# arduino.net
KiCad netlist of a schematic drawn in EAGLE
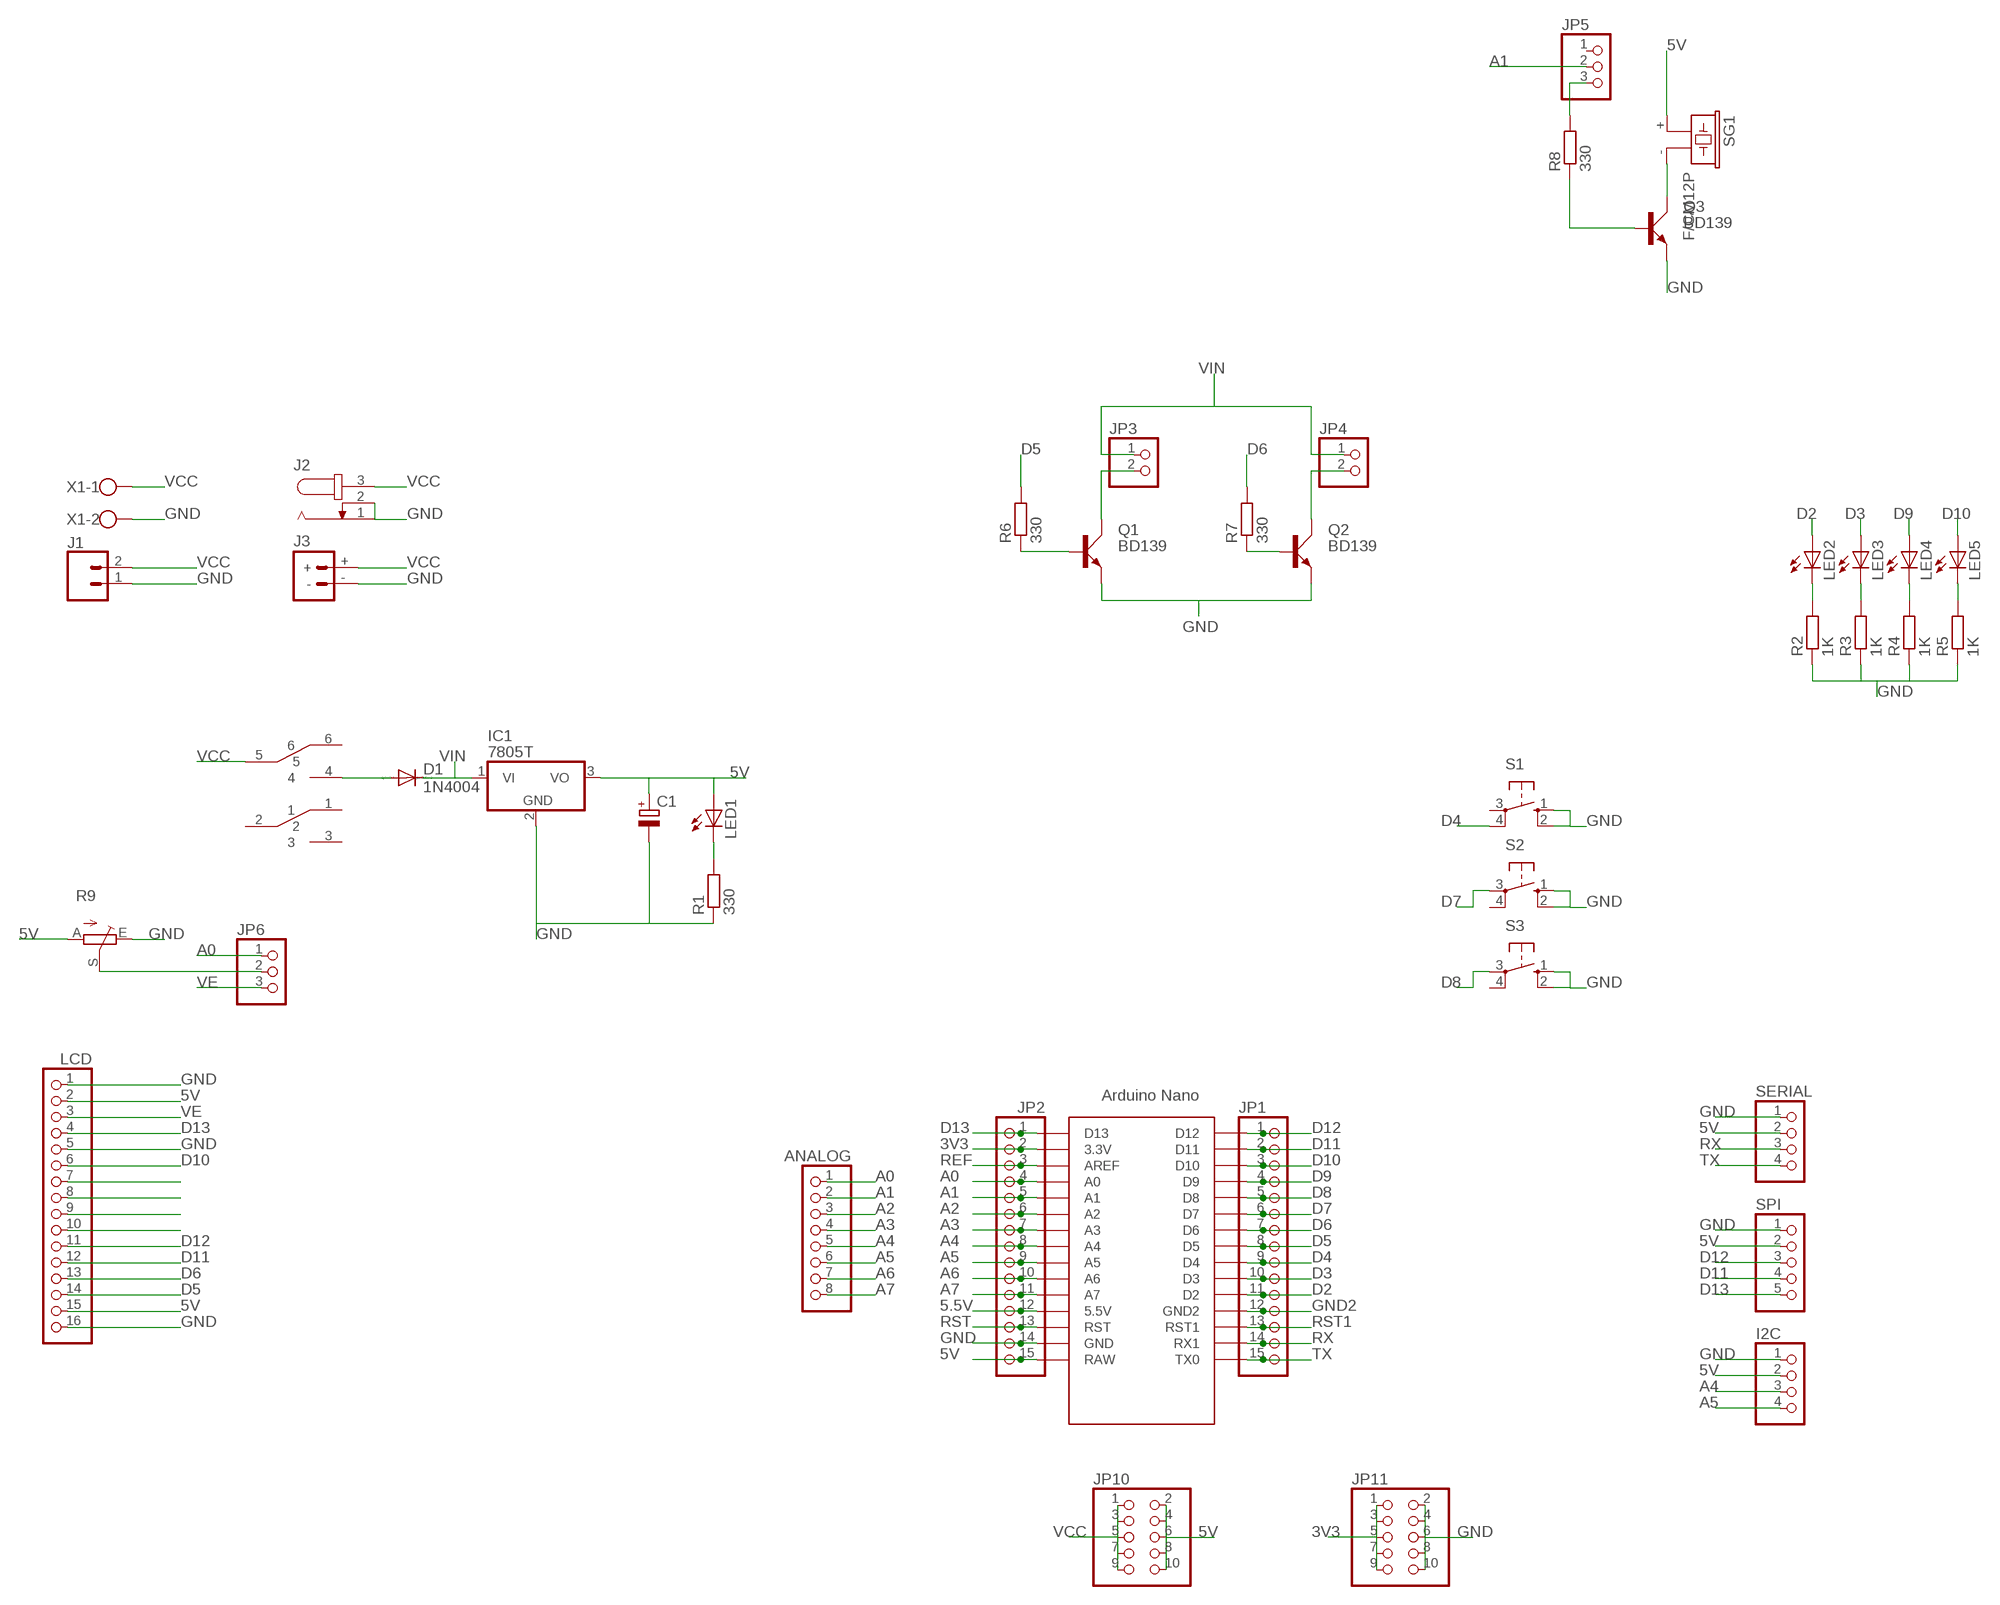
[diagram p0: schematic, sheet 1]

(export (version "E")
  (design (tool "Eeschema 10.0.6"))
  (components
    (comp (ref "ANALOG")
      (value "PINHD-1X8")
      (footprint "eagle-import:1X08")
      (libsource (lib "eagle-import") (part "PINHD-1X8"))
    )
    (comp (ref "C1")
      (value "CPOL-EUE5-8.5")
      (footprint "eagle-import:E5-8,5")
      (libsource (lib "eagle-import") (part "CPOL-EUE5-8.5"))
    )
    (comp (ref "D1")
      (value "1N4004")
      (footprint "eagle-import:DO41-10")
      (libsource (lib "eagle-import") (part "1N4004"))
    )
    (comp (ref "I2C")
      (value "PINHD-1X4")
      (footprint "eagle-import:1X04")
      (libsource (lib "eagle-import") (part "PINHD-1X4"))
    )
    (comp (ref "IC1")
      (value "7805T")
      (footprint "eagle-import:TO220H")
      (libsource (lib "eagle-import") (part "78T05"))
    )
    (comp (ref "J1")
      (value "CONN_02POLAR_LOCK")
      (footprint "eagle-import:MOLEX-1X2_LOCK")
      (libsource (lib "eagle-import") (part "CONN_02POLAR_LOCK"))
    )
    (comp (ref "J2")
      (value "JACK-PLUG0")
      (footprint "eagle-import:SPC4077")
      (libsource (lib "eagle-import") (part "JACK-PLUG0"))
    )
    (comp (ref "J3")
      (value "BATTERY_CONN_DEANS")
      (footprint "eagle-import:DEANS")
      (libsource (lib "eagle-import") (part "BATTERY_CONN_DEANS"))
    )
    (comp (ref "JP1")
      (value "PINHD-1X15")
      (footprint "eagle-import:1X15")
      (libsource (lib "eagle-import") (part "PINHD-1X15"))
    )
    (comp (ref "JP2")
      (value "PINHD-1X15")
      (footprint "eagle-import:1X15")
      (libsource (lib "eagle-import") (part "PINHD-1X15"))
    )
    (comp (ref "JP3")
      (value "PINHD-1X2")
      (footprint "eagle-import:1X02")
      (libsource (lib "eagle-import") (part "PINHD-1X2"))
    )
    (comp (ref "JP4")
      (value "PINHD-1X2")
      (footprint "eagle-import:1X02")
      (libsource (lib "eagle-import") (part "PINHD-1X2"))
    )
    (comp (ref "JP5")
      (value "PINHD-1X3")
      (footprint "eagle-import:1X03")
      (libsource (lib "eagle-import") (part "PINHD-1X3"))
    )
    (comp (ref "JP6")
      (value "PINHD-1X3")
      (footprint "eagle-import:1X03")
      (libsource (lib "eagle-import") (part "PINHD-1X3"))
    )
    (comp (ref "JP10")
      (value "PINHD-2X5")
      (footprint "eagle-import:2X05")
      (libsource (lib "eagle-import") (part "PINHD-2X5"))
    )
    (comp (ref "JP11")
      (value "PINHD-2X5")
      (footprint "eagle-import:2X05")
      (libsource (lib "eagle-import") (part "PINHD-2X5"))
    )
    (comp (ref "LCD")
      (value "PINHD-1X16")
      (footprint "eagle-import:1X16")
      (libsource (lib "eagle-import") (part "PINHD-1X16"))
    )
    (comp (ref "LED1")
      (value "LED3MM")
      (footprint "eagle-import:LED3MM")
      (libsource (lib "eagle-import") (part "LED3MM"))
    )
    (comp (ref "LED2")
      (value "LED3MM")
      (footprint "eagle-import:LED3MM")
      (libsource (lib "eagle-import") (part "LED3MM"))
    )
    (comp (ref "LED3")
      (value "LED3MM")
      (footprint "eagle-import:LED3MM")
      (libsource (lib "eagle-import") (part "LED3MM"))
    )
    (comp (ref "LED4")
      (value "LED3MM")
      (footprint "eagle-import:LED3MM")
      (libsource (lib "eagle-import") (part "LED3MM"))
    )
    (comp (ref "LED5")
      (value "LED3MM")
      (footprint "eagle-import:LED3MM")
      (libsource (lib "eagle-import") (part "LED3MM"))
    )
    (comp (ref "Q1")
      (value "BD139")
      (footprint "eagle-import:TO126AV")
      (libsource (lib "eagle-import") (part "BD139"))
    )
    (comp (ref "Q2")
      (value "BD139")
      (footprint "eagle-import:TO126AV")
      (libsource (lib "eagle-import") (part "BD139"))
    )
    (comp (ref "Q3")
      (value "BD139")
      (footprint "eagle-import:TO126AV")
      (libsource (lib "eagle-import") (part "BD139"))
    )
    (comp (ref "R1")
      (value "330")
      (footprint "eagle-import:0207_7")
      (libsource (lib "eagle-import") (part "R-EU_0207/7"))
    )
    (comp (ref "R2")
      (value "1K")
      (footprint "eagle-import:0207_7")
      (libsource (lib "eagle-import") (part "R-EU_0207/7"))
    )
    (comp (ref "R3")
      (value "1K")
      (footprint "eagle-import:0207_7")
      (libsource (lib "eagle-import") (part "R-EU_0207/7"))
    )
    (comp (ref "R4")
      (value "1K")
      (footprint "eagle-import:0207_7")
      (libsource (lib "eagle-import") (part "R-EU_0207/7"))
    )
    (comp (ref "R5")
      (value "1K")
      (footprint "eagle-import:0207_7")
      (libsource (lib "eagle-import") (part "R-EU_0207/7"))
    )
    (comp (ref "R6")
      (value "330")
      (footprint "eagle-import:0207_7")
      (libsource (lib "eagle-import") (part "R-EU_0207/7"))
    )
    (comp (ref "R7")
      (value "330")
      (footprint "eagle-import:0207_7")
      (libsource (lib "eagle-import") (part "R-EU_0207/7"))
    )
    (comp (ref "R8")
      (value "330")
      (footprint "eagle-import:0207_7")
      (libsource (lib "eagle-import") (part "R-EU_0207/7"))
    )
    (comp (ref "R9")
      (value "TRIM_EU-CA6V")
      (footprint "eagle-import:CA6V")
      (libsource (lib "eagle-import") (part "TRIM_EU-CA6V"))
    )
    (comp (ref "S1")
      (value "10-XX")
      (footprint "eagle-import:B3F-10XX")
      (fields (field (name "MPN") "B3F-1000"))
      (libsource (lib "eagle-import") (part "10-XX"))
    )
    (comp (ref "S2")
      (value "10-XX")
      (footprint "eagle-import:B3F-10XX")
      (fields (field (name "MPN") "B3F-1000"))
      (libsource (lib "eagle-import") (part "10-XX"))
    )
    (comp (ref "S3")
      (value "10-XX")
      (footprint "eagle-import:B3F-10XX")
      (fields (field (name "MPN") "B3F-1000"))
      (libsource (lib "eagle-import") (part "10-XX"))
    )
    (comp (ref "SERIAL")
      (value "PINHD-1X4")
      (footprint "eagle-import:1X04")
      (libsource (lib "eagle-import") (part "PINHD-1X4"))
    )
    (comp (ref "SG1")
      (value "F/CM12P")
      (footprint "eagle-import:F_CM12P")
      (libsource (lib "eagle-import") (part "F/CM12P"))
    )
    (comp (ref "SPI")
      (value "PINHD-1X5")
      (footprint "eagle-import:1X05")
      (libsource (lib "eagle-import") (part "PINHD-1X5"))
    )
    (comp (ref "U$1")
      (value "NANO")
      (footprint "eagle-import:NANO")
      (libsource (lib "eagle-import") (part "NANO"))
    )
    (comp (ref "U$2")
      (value "BUTTON-DPDT-7MM")
      (footprint "eagle-import:BUTTON-DPDT-7MM")
      (libsource (lib "eagle-import") (part "BUTTON-DPDT-7MM"))
    )
    (comp (ref "X1")
      (value "W237-102")
      (footprint "eagle-import:W237-102")
      (fields (field (name "MPN") "237-102"))
      (libsource (lib "eagle-import") (part "W237-102"))
    )
  )
  (nets
    (net (code "1") (name "/3V3") (class "Default")
      (node (ref "JP11") (pin "1") (pinfunction "1_1") (pintype "passive"))
      (node (ref "JP11") (pin "3") (pinfunction "3_3") (pintype "passive"))
      (node (ref "JP11") (pin "5") (pinfunction "5_5") (pintype "passive"))
      (node (ref "JP11") (pin "7") (pinfunction "7_7") (pintype "passive"))
      (node (ref "JP11") (pin "9") (pinfunction "9_9") (pintype "passive"))
      (node (ref "JP2") (pin "2") (pinfunction "2_2") (pintype "passive"))
      (node (ref "U$1") (pin "3.3V") (pinfunction "3.3V_3.3V") (pintype "bidirectional"))
    )
    (net (code "2") (name "/5.5V") (class "Default")
      (node (ref "JP2") (pin "12") (pinfunction "12_12") (pintype "passive"))
      (node (ref "U$1") (pin "5V") (pinfunction "5.5V_5V") (pintype "bidirectional"))
    )
    (net (code "3") (name "/5V") (class "Default")
      (node (ref "C1") (pin "+") (pinfunction "+_+") (pintype "passive"))
      (node (ref "I2C") (pin "2") (pinfunction "2_2") (pintype "passive"))
      (node (ref "IC1") (pin "3") (pinfunction "VO_3") (pintype "passive"))
      (node (ref "JP10") (pin "10") (pinfunction "10_10") (pintype "passive"))
      (node (ref "JP10") (pin "2") (pinfunction "2_2") (pintype "passive"))
      (node (ref "JP10") (pin "4") (pinfunction "4_4") (pintype "passive"))
      (node (ref "JP10") (pin "6") (pinfunction "6_6") (pintype "passive"))
      (node (ref "JP10") (pin "8") (pinfunction "8_8") (pintype "passive"))
      (node (ref "JP2") (pin "15") (pinfunction "15_15") (pintype "passive"))
      (node (ref "LCD") (pin "15") (pinfunction "15_15") (pintype "passive"))
      (node (ref "LCD") (pin "2") (pinfunction "2_2") (pintype "passive"))
      (node (ref "LED1") (pin "A") (pinfunction "A_A") (pintype "passive"))
      (node (ref "R9") (pin "A") (pinfunction "A_A") (pintype "passive"))
      (node (ref "SERIAL") (pin "2") (pinfunction "2_2") (pintype "passive"))
      (node (ref "SG1") (pin "+") (pinfunction "1_+") (pintype "passive"))
      (node (ref "SPI") (pin "2") (pinfunction "2_2") (pintype "passive"))
      (node (ref "U$1") (pin "RAW") (pinfunction "RAW_RAW") (pintype "bidirectional"))
    )
    (net (code "4") (name "/A0") (class "Default")
      (node (ref "ANALOG") (pin "1") (pinfunction "1_1") (pintype "passive"))
      (node (ref "JP2") (pin "4") (pinfunction "4_4") (pintype "passive"))
      (node (ref "JP6") (pin "1") (pinfunction "1_1") (pintype "passive"))
      (node (ref "U$1") (pin "A0") (pinfunction "A0_A0") (pintype "bidirectional"))
    )
    (net (code "5") (name "/A1") (class "Default")
      (node (ref "ANALOG") (pin "2") (pinfunction "2_2") (pintype "passive"))
      (node (ref "JP2") (pin "5") (pinfunction "5_5") (pintype "passive"))
      (node (ref "JP5") (pin "2") (pinfunction "2_2") (pintype "passive"))
      (node (ref "U$1") (pin "A1") (pinfunction "A1_A1") (pintype "bidirectional"))
    )
    (net (code "6") (name "/A2") (class "Default")
      (node (ref "ANALOG") (pin "3") (pinfunction "3_3") (pintype "passive"))
      (node (ref "JP2") (pin "6") (pinfunction "6_6") (pintype "passive"))
      (node (ref "U$1") (pin "A2") (pinfunction "A2_A2") (pintype "bidirectional"))
    )
    (net (code "7") (name "/A3") (class "Default")
      (node (ref "ANALOG") (pin "4") (pinfunction "4_4") (pintype "passive"))
      (node (ref "JP2") (pin "7") (pinfunction "7_7") (pintype "passive"))
      (node (ref "U$1") (pin "A3") (pinfunction "A3_A3") (pintype "bidirectional"))
    )
    (net (code "8") (name "/A4") (class "Default")
      (node (ref "ANALOG") (pin "5") (pinfunction "5_5") (pintype "passive"))
      (node (ref "I2C") (pin "3") (pinfunction "3_3") (pintype "passive"))
      (node (ref "JP2") (pin "8") (pinfunction "8_8") (pintype "passive"))
      (node (ref "U$1") (pin "A4") (pinfunction "A4_A4") (pintype "bidirectional"))
    )
    (net (code "9") (name "/A5") (class "Default")
      (node (ref "ANALOG") (pin "6") (pinfunction "6_6") (pintype "passive"))
      (node (ref "I2C") (pin "4") (pinfunction "4_4") (pintype "passive"))
      (node (ref "JP2") (pin "9") (pinfunction "9_9") (pintype "passive"))
      (node (ref "U$1") (pin "A5") (pinfunction "A5_A5") (pintype "bidirectional"))
    )
    (net (code "10") (name "/A6") (class "Default")
      (node (ref "ANALOG") (pin "7") (pinfunction "7_7") (pintype "passive"))
      (node (ref "JP2") (pin "10") (pinfunction "10_10") (pintype "passive"))
      (node (ref "U$1") (pin "A6") (pinfunction "A6_A6") (pintype "bidirectional"))
    )
    (net (code "11") (name "/A7") (class "Default")
      (node (ref "ANALOG") (pin "8") (pinfunction "8_8") (pintype "passive"))
      (node (ref "JP2") (pin "11") (pinfunction "11_11") (pintype "passive"))
      (node (ref "U$1") (pin "A7") (pinfunction "A7_A7") (pintype "bidirectional"))
    )
    (net (code "12") (name "/D2") (class "Default")
      (node (ref "JP1") (pin "11") (pinfunction "11_11") (pintype "passive"))
      (node (ref "LED2") (pin "A") (pinfunction "A_A") (pintype "passive"))
      (node (ref "U$1") (pin "D2") (pinfunction "D2_D2") (pintype "bidirectional"))
    )
    (net (code "13") (name "/D3") (class "Default")
      (node (ref "JP1") (pin "10") (pinfunction "10_10") (pintype "passive"))
      (node (ref "LED3") (pin "A") (pinfunction "A_A") (pintype "passive"))
      (node (ref "U$1") (pin "D3") (pinfunction "D3_D3") (pintype "bidirectional"))
    )
    (net (code "14") (name "/D4") (class "Default")
      (node (ref "JP1") (pin "9") (pinfunction "9_9") (pintype "passive"))
      (node (ref "S1") (pin "4") (pinfunction "P1_4") (pintype "passive"))
      (node (ref "U$1") (pin "D4") (pinfunction "D4_D4") (pintype "bidirectional"))
    )
    (net (code "15") (name "/D5") (class "Default")
      (node (ref "JP1") (pin "8") (pinfunction "8_8") (pintype "passive"))
      (node (ref "LCD") (pin "14") (pinfunction "14_14") (pintype "passive"))
      (node (ref "R6") (pin "2") (pinfunction "2_2") (pintype "passive"))
      (node (ref "U$1") (pin "D5") (pinfunction "D5_D5") (pintype "bidirectional"))
    )
    (net (code "16") (name "/D6") (class "Default")
      (node (ref "JP1") (pin "7") (pinfunction "7_7") (pintype "passive"))
      (node (ref "LCD") (pin "13") (pinfunction "13_13") (pintype "passive"))
      (node (ref "R7") (pin "2") (pinfunction "2_2") (pintype "passive"))
      (node (ref "U$1") (pin "D6") (pinfunction "D6_D6") (pintype "bidirectional"))
    )
    (net (code "17") (name "/D7") (class "Default")
      (node (ref "JP1") (pin "6") (pinfunction "6_6") (pintype "passive"))
      (node (ref "S2") (pin "3") (pinfunction "P_3") (pintype "passive"))
      (node (ref "U$1") (pin "D7") (pinfunction "D7_D7") (pintype "bidirectional"))
    )
    (net (code "18") (name "/D8") (class "Default")
      (node (ref "JP1") (pin "5") (pinfunction "5_5") (pintype "passive"))
      (node (ref "S3") (pin "3") (pinfunction "P_3") (pintype "passive"))
      (node (ref "U$1") (pin "D8") (pinfunction "D8_D8") (pintype "bidirectional"))
    )
    (net (code "19") (name "/D9") (class "Default")
      (node (ref "JP1") (pin "4") (pinfunction "4_4") (pintype "passive"))
      (node (ref "LED4") (pin "A") (pinfunction "A_A") (pintype "passive"))
      (node (ref "U$1") (pin "D9") (pinfunction "D9_D9") (pintype "bidirectional"))
    )
    (net (code "20") (name "/D10") (class "Default")
      (node (ref "JP1") (pin "3") (pinfunction "3_3") (pintype "passive"))
      (node (ref "LCD") (pin "6") (pinfunction "6_6") (pintype "passive"))
      (node (ref "LED5") (pin "A") (pinfunction "A_A") (pintype "passive"))
      (node (ref "U$1") (pin "D10") (pinfunction "D10_D10") (pintype "bidirectional"))
    )
    (net (code "21") (name "/D11") (class "Default")
      (node (ref "JP1") (pin "2") (pinfunction "2_2") (pintype "passive"))
      (node (ref "LCD") (pin "12") (pinfunction "12_12") (pintype "passive"))
      (node (ref "SPI") (pin "4") (pinfunction "4_4") (pintype "passive"))
      (node (ref "U$1") (pin "D11") (pinfunction "D11_D11") (pintype "bidirectional"))
    )
    (net (code "22") (name "/D12") (class "Default")
      (node (ref "JP1") (pin "1") (pinfunction "1_1") (pintype "passive"))
      (node (ref "LCD") (pin "11") (pinfunction "11_11") (pintype "passive"))
      (node (ref "SPI") (pin "3") (pinfunction "3_3") (pintype "passive"))
      (node (ref "U$1") (pin "D12") (pinfunction "D12_D12") (pintype "bidirectional"))
    )
    (net (code "23") (name "/D13") (class "Default")
      (node (ref "JP2") (pin "1") (pinfunction "1_1") (pintype "passive"))
      (node (ref "LCD") (pin "4") (pinfunction "4_4") (pintype "passive"))
      (node (ref "SPI") (pin "5") (pinfunction "5_5") (pintype "passive"))
      (node (ref "U$1") (pin "D13") (pinfunction "D13_D13") (pintype "bidirectional"))
    )
    (net (code "24") (name "/GND") (class "Default")
      (node (ref "C1") (pin "-") (pinfunction "-_-") (pintype "passive"))
      (node (ref "I2C") (pin "1") (pinfunction "1_1") (pintype "passive"))
      (node (ref "IC1") (pin "2") (pinfunction "GND_2") (pintype "passive"))
      (node (ref "J1") (pin "1") (pinfunction "1_1") (pintype "passive"))
      (node (ref "J2") (pin "1") (pinfunction "1_1") (pintype "passive"))
      (node (ref "J2") (pin "2") (pinfunction "2_2") (pintype "passive"))
      (node (ref "J3") (pin "-") (pinfunction "-_-") (pintype "passive"))
      (node (ref "JP11") (pin "10") (pinfunction "10_10") (pintype "passive"))
      (node (ref "JP11") (pin "2") (pinfunction "2_2") (pintype "passive"))
      (node (ref "JP11") (pin "4") (pinfunction "4_4") (pintype "passive"))
      (node (ref "JP11") (pin "6") (pinfunction "6_6") (pintype "passive"))
      (node (ref "JP11") (pin "8") (pinfunction "8_8") (pintype "passive"))
      (node (ref "JP2") (pin "14") (pinfunction "14_14") (pintype "passive"))
      (node (ref "LCD") (pin "1") (pinfunction "1_1") (pintype "passive"))
      (node (ref "LCD") (pin "16") (pinfunction "16_16") (pintype "passive"))
      (node (ref "LCD") (pin "5") (pinfunction "5_5") (pintype "passive"))
      (node (ref "Q1") (pin "E") (pinfunction "E_E") (pintype "passive"))
      (node (ref "Q2") (pin "E") (pinfunction "E_E") (pintype "passive"))
      (node (ref "Q3") (pin "E") (pinfunction "E_E") (pintype "passive"))
      (node (ref "R1") (pin "1") (pinfunction "1_1") (pintype "passive"))
      (node (ref "R2") (pin "1") (pinfunction "1_1") (pintype "passive"))
      (node (ref "R3") (pin "1") (pinfunction "1_1") (pintype "passive"))
      (node (ref "R4") (pin "1") (pinfunction "1_1") (pintype "passive"))
      (node (ref "R5") (pin "1") (pinfunction "1_1") (pintype "passive"))
      (node (ref "R9") (pin "E") (pinfunction "E_E") (pintype "passive"))
      (node (ref "S1") (pin "1") (pinfunction "S_1") (pintype "passive"))
      (node (ref "S1") (pin "2") (pinfunction "S1_2") (pintype "passive"))
      (node (ref "S2") (pin "1") (pinfunction "S_1") (pintype "passive"))
      (node (ref "S2") (pin "2") (pinfunction "S1_2") (pintype "passive"))
      (node (ref "S3") (pin "1") (pinfunction "S_1") (pintype "passive"))
      (node (ref "S3") (pin "2") (pinfunction "S1_2") (pintype "passive"))
      (node (ref "SERIAL") (pin "1") (pinfunction "1_1") (pintype "passive"))
      (node (ref "SPI") (pin "1") (pinfunction "1_1") (pintype "passive"))
      (node (ref "U$1") (pin "GND") (pinfunction "GND_GND") (pintype "bidirectional"))
      (node (ref "X1") (pin "2") (pinfunction "KL_2") (pintype "passive"))
    )
    (net (code "25") (name "/GND2") (class "Default")
      (node (ref "JP1") (pin "12") (pinfunction "12_12") (pintype "passive"))
      (node (ref "U$1") (pin "GND1") (pinfunction "GND2_GND1") (pintype "bidirectional"))
    )
    (net (code "26") (name "/REF") (class "Default")
      (node (ref "JP2") (pin "3") (pinfunction "3_3") (pintype "passive"))
      (node (ref "U$1") (pin "AREF") (pinfunction "AREF_AREF") (pintype "bidirectional"))
    )
    (net (code "27") (name "/RST") (class "Default")
      (node (ref "JP2") (pin "13") (pinfunction "13_13") (pintype "passive"))
      (node (ref "U$1") (pin "RST") (pinfunction "RST_RST") (pintype "bidirectional"))
    )
    (net (code "28") (name "/RST1") (class "Default")
      (node (ref "JP1") (pin "13") (pinfunction "13_13") (pintype "passive"))
      (node (ref "U$1") (pin "RST1") (pinfunction "RST1_RST1") (pintype "bidirectional"))
    )
    (net (code "29") (name "/RX") (class "Default")
      (node (ref "JP1") (pin "14") (pinfunction "14_14") (pintype "passive"))
      (node (ref "SERIAL") (pin "3") (pinfunction "3_3") (pintype "passive"))
      (node (ref "U$1") (pin "RX1") (pinfunction "RX1_RX1") (pintype "bidirectional"))
    )
    (net (code "30") (name "/TX") (class "Default")
      (node (ref "JP1") (pin "15") (pinfunction "15_15") (pintype "passive"))
      (node (ref "SERIAL") (pin "4") (pinfunction "4_4") (pintype "passive"))
      (node (ref "U$1") (pin "TX0") (pinfunction "TX0_TX0") (pintype "bidirectional"))
    )
    (net (code "31") (name "/VCC") (class "Default")
      (node (ref "J1") (pin "2") (pinfunction "2_2") (pintype "passive"))
      (node (ref "J2") (pin "3") (pinfunction "3_3") (pintype "passive"))
      (node (ref "J3") (pin "+") (pinfunction "+_+") (pintype "passive"))
      (node (ref "JP10") (pin "1") (pinfunction "1_1") (pintype "passive"))
      (node (ref "JP10") (pin "3") (pinfunction "3_3") (pintype "passive"))
      (node (ref "JP10") (pin "5") (pinfunction "5_5") (pintype "passive"))
      (node (ref "JP10") (pin "7") (pinfunction "7_7") (pintype "passive"))
      (node (ref "JP10") (pin "9") (pinfunction "9_9") (pintype "passive"))
      (node (ref "U$2") (pin "5") (pinfunction "5_5") (pintype "bidirectional"))
      (node (ref "X1") (pin "1") (pinfunction "KL_1") (pintype "passive"))
    )
    (net (code "32") (name "/VE") (class "Default")
      (node (ref "JP6") (pin "3") (pinfunction "3_3") (pintype "passive"))
      (node (ref "LCD") (pin "3") (pinfunction "3_3") (pintype "passive"))
    )
    (net (code "33") (name "/VIN") (class "Default")
      (node (ref "D1") (pin "C") (pinfunction "C_C") (pintype "passive"))
      (node (ref "IC1") (pin "1") (pinfunction "VI_1") (pintype "input"))
      (node (ref "JP3") (pin "1") (pinfunction "1_1") (pintype "passive"))
      (node (ref "JP4") (pin "1") (pinfunction "1_1") (pintype "passive"))
    )
    (net (code "34") (name "Net-(D1-PadA)") (class "Default")
      (node (ref "D1") (pin "A") (pinfunction "A_A") (pintype "passive"))
      (node (ref "U$2") (pin "4") (pinfunction "4_4") (pintype "bidirectional"))
    )
    (net (code "35") (name "Net-(JP3-Pad2)") (class "Default")
      (node (ref "JP3") (pin "2") (pinfunction "2_2") (pintype "passive"))
      (node (ref "Q1") (pin "C") (pinfunction "C_C") (pintype "passive"))
    )
    (net (code "36") (name "Net-(JP4-Pad2)") (class "Default")
      (node (ref "JP4") (pin "2") (pinfunction "2_2") (pintype "passive"))
      (node (ref "Q2") (pin "C") (pinfunction "C_C") (pintype "passive"))
    )
    (net (code "37") (name "Net-(JP5-Pad3)") (class "Default")
      (node (ref "JP5") (pin "3") (pinfunction "3_3") (pintype "passive"))
      (node (ref "R8") (pin "2") (pinfunction "2_2") (pintype "passive"))
    )
    (net (code "38") (name "Net-(JP6-Pad2)") (class "Default")
      (node (ref "JP6") (pin "2") (pinfunction "2_2") (pintype "passive"))
      (node (ref "R9") (pin "S") (pinfunction "S_S") (pintype "passive"))
    )
    (net (code "39") (name "Net-(LED1-C)") (class "Default")
      (node (ref "LED1") (pin "K") (pinfunction "C_K") (pintype "passive"))
      (node (ref "R1") (pin "2") (pinfunction "2_2") (pintype "passive"))
    )
    (net (code "40") (name "Net-(LED2-C)") (class "Default")
      (node (ref "LED2") (pin "K") (pinfunction "C_K") (pintype "passive"))
      (node (ref "R2") (pin "2") (pinfunction "2_2") (pintype "passive"))
    )
    (net (code "41") (name "Net-(LED3-C)") (class "Default")
      (node (ref "LED3") (pin "K") (pinfunction "C_K") (pintype "passive"))
      (node (ref "R3") (pin "2") (pinfunction "2_2") (pintype "passive"))
    )
    (net (code "42") (name "Net-(LED4-C)") (class "Default")
      (node (ref "LED4") (pin "K") (pinfunction "C_K") (pintype "passive"))
      (node (ref "R4") (pin "2") (pinfunction "2_2") (pintype "passive"))
    )
    (net (code "43") (name "Net-(LED5-C)") (class "Default")
      (node (ref "LED5") (pin "K") (pinfunction "C_K") (pintype "passive"))
      (node (ref "R5") (pin "2") (pinfunction "2_2") (pintype "passive"))
    )
    (net (code "44") (name "Net-(Q1-PadB)") (class "Default")
      (node (ref "Q1") (pin "B") (pinfunction "B_B") (pintype "passive"))
      (node (ref "R6") (pin "1") (pinfunction "1_1") (pintype "passive"))
    )
    (net (code "45") (name "Net-(Q2-PadB)") (class "Default")
      (node (ref "Q2") (pin "B") (pinfunction "B_B") (pintype "passive"))
      (node (ref "R7") (pin "1") (pinfunction "1_1") (pintype "passive"))
    )
    (net (code "46") (name "Net-(Q3-PadB)") (class "Default")
      (node (ref "Q3") (pin "B") (pinfunction "B_B") (pintype "passive"))
      (node (ref "R8") (pin "1") (pinfunction "1_1") (pintype "passive"))
    )
    (net (code "47") (name "Net-(SG1-2)") (class "Default")
      (node (ref "Q3") (pin "C") (pinfunction "C_C") (pintype "passive"))
      (node (ref "SG1") (pin "-") (pinfunction "2_-") (pintype "passive"))
    )
    (net (code "48") (name "unconnected-(JP5-Pad1)") (class "Default")
      (node (ref "JP5") (pin "1") (pinfunction "1_1") (pintype "passive"))
    )
    (net (code "49") (name "unconnected-(LCD-Pad7)") (class "Default")
      (node (ref "LCD") (pin "7") (pinfunction "7_7") (pintype "passive"))
    )
    (net (code "50") (name "unconnected-(LCD-Pad8)") (class "Default")
      (node (ref "LCD") (pin "8") (pinfunction "8_8") (pintype "passive"))
    )
    (net (code "51") (name "unconnected-(LCD-Pad9)") (class "Default")
      (node (ref "LCD") (pin "9") (pinfunction "9_9") (pintype "passive"))
    )
    (net (code "52") (name "unconnected-(LCD-Pad10)") (class "Default")
      (node (ref "LCD") (pin "10") (pinfunction "10_10") (pintype "passive"))
    )
    (net (code "53") (name "unconnected-(S1-P-Pad3)") (class "Default")
      (node (ref "S1") (pin "3") (pinfunction "P_3") (pintype "passive"))
    )
    (net (code "54") (name "unconnected-(S2-P1-Pad4)") (class "Default")
      (node (ref "S2") (pin "4") (pinfunction "P1_4") (pintype "passive"))
    )
    (net (code "55") (name "unconnected-(S3-P1-Pad4)") (class "Default")
      (node (ref "S3") (pin "4") (pinfunction "P1_4") (pintype "passive"))
    )
    (net (code "56") (name "unconnected-(U$1-PadICSP1)") (class "Default")
      (node (ref "U$1") (pin "ICSP1") (pinfunction "ICSP1_ICSP1") (pintype "bidirectional"))
    )
    (net (code "57") (name "unconnected-(U$1-PadICSP2)") (class "Default")
      (node (ref "U$1") (pin "ICSP2") (pinfunction "ICSP2_ICSP2") (pintype "bidirectional"))
    )
    (net (code "58") (name "unconnected-(U$1-PadICSP3)") (class "Default")
      (node (ref "U$1") (pin "ICSP3") (pinfunction "ICSP3_ICSP3") (pintype "bidirectional"))
    )
    (net (code "59") (name "unconnected-(U$1-PadICSP4)") (class "Default")
      (node (ref "U$1") (pin "ICSP4") (pinfunction "ICSP4_ICSP4") (pintype "bidirectional"))
    )
    (net (code "60") (name "unconnected-(U$1-PadICSP5)") (class "Default")
      (node (ref "U$1") (pin "ICSP5") (pinfunction "ICSP5_ICSP5") (pintype "bidirectional"))
    )
    (net (code "61") (name "unconnected-(U$1-PadICSP6)") (class "Default")
      (node (ref "U$1") (pin "ICSP6") (pinfunction "ICSP6_ICSP6") (pintype "bidirectional"))
    )
    (net (code "62") (name "unconnected-(U$2-Pad1)") (class "Default")
      (node (ref "U$2") (pin "1") (pinfunction "1_1") (pintype "bidirectional"))
    )
    (net (code "63") (name "unconnected-(U$2-Pad2)") (class "Default")
      (node (ref "U$2") (pin "2") (pinfunction "2_2") (pintype "bidirectional"))
    )
    (net (code "64") (name "unconnected-(U$2-Pad3)") (class "Default")
      (node (ref "U$2") (pin "3") (pinfunction "3_3") (pintype "bidirectional"))
    )
    (net (code "65") (name "unconnected-(U$2-Pad6)") (class "Default")
      (node (ref "U$2") (pin "6") (pinfunction "6_6") (pintype "bidirectional"))
    )
  )
)
